# infant.net
KiCad netlist of a schematic drawn in EAGLE
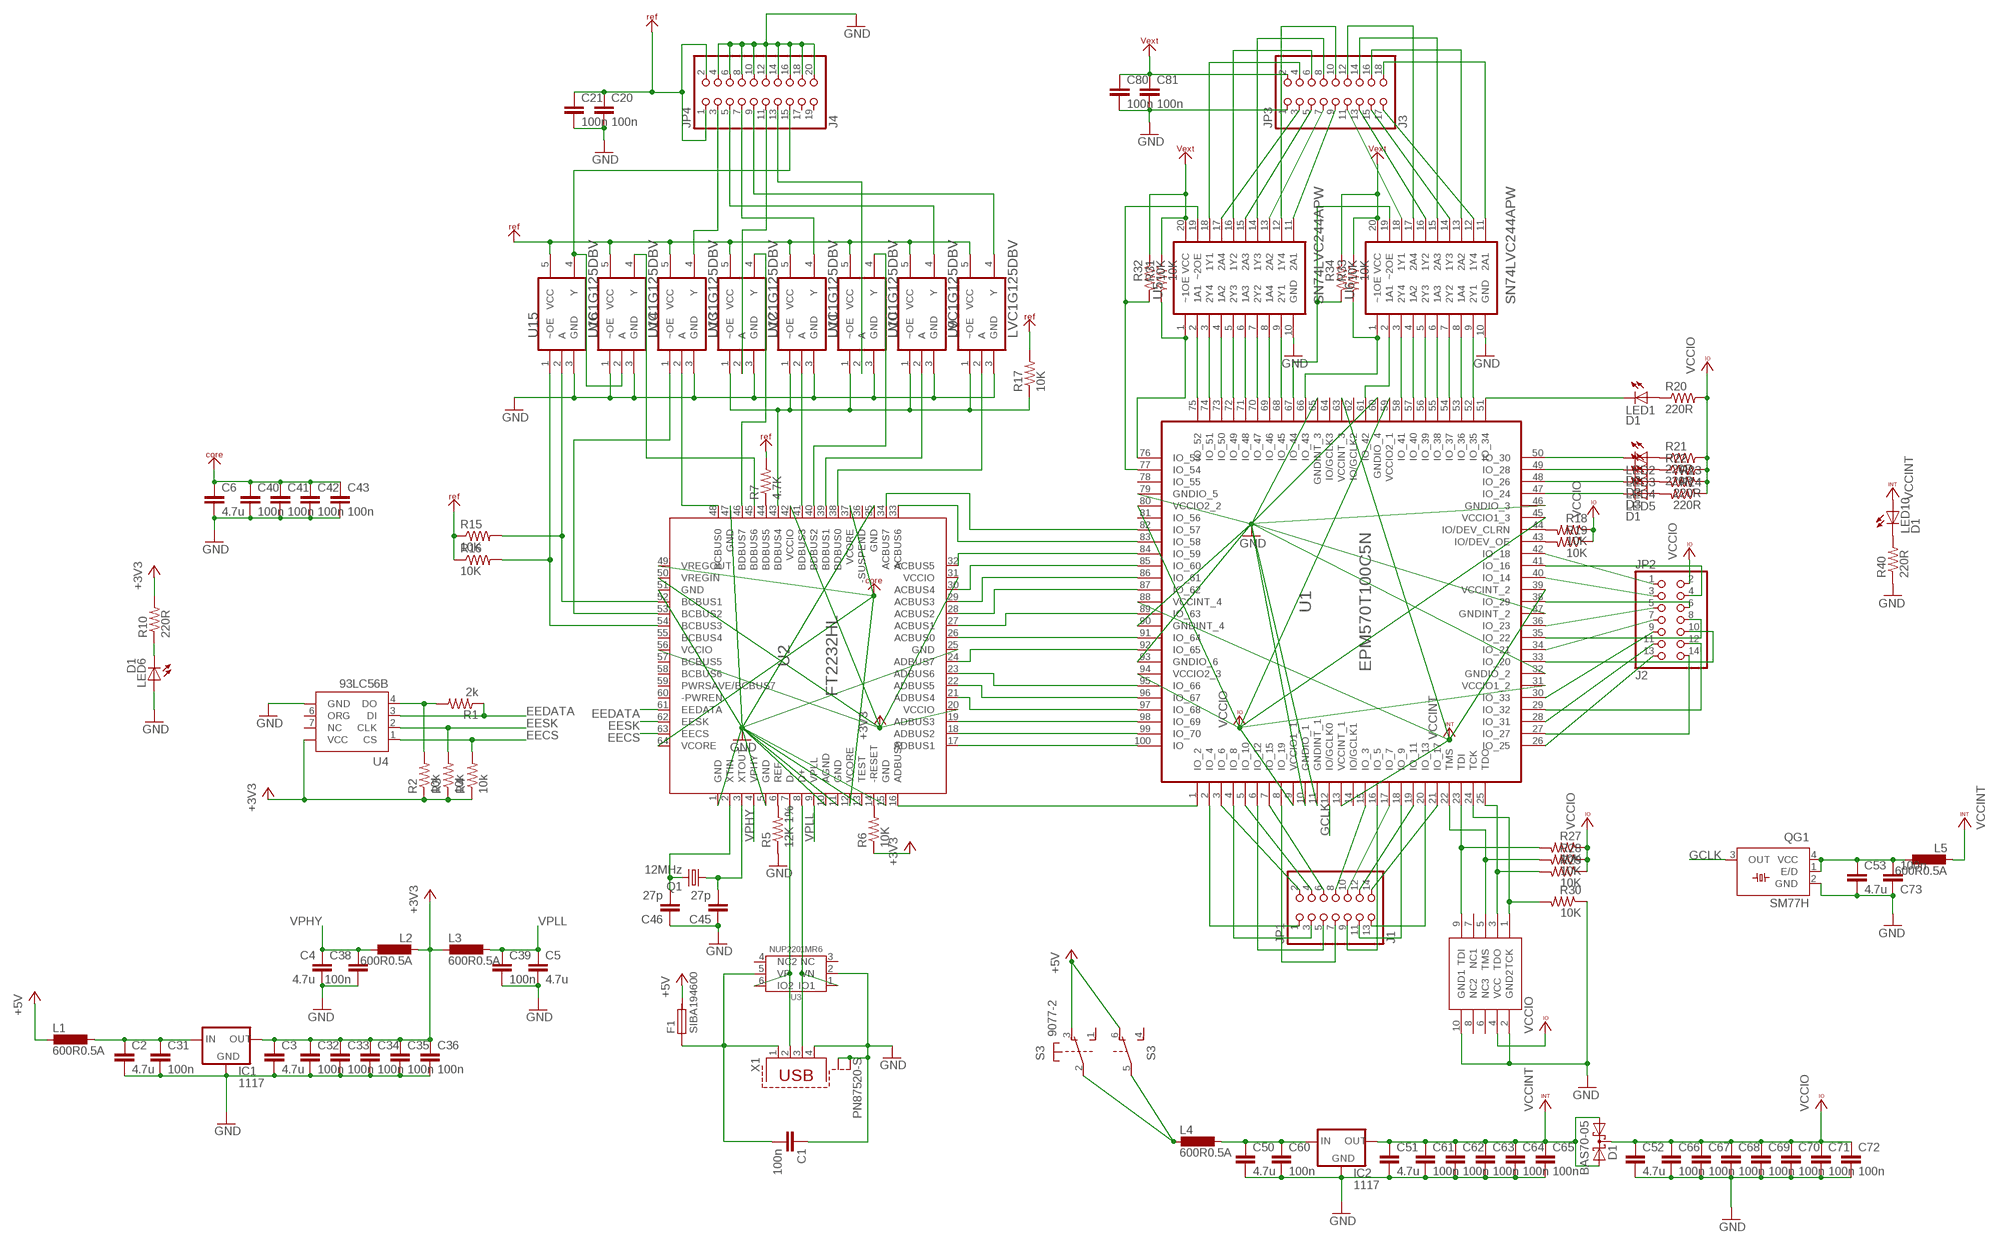
[diagram p0: schematic, sheet 1]

(export (version "E")
  (design (tool "Eeschema 10.0.6"))
  (components
    (comp (ref "C1")
      (value "100n")
      (footprint "eagle-import:C0805")
      (libsource (lib "eagle-import") (part "C-EUC0805"))
    )
    (comp (ref "C2")
      (value "4.7u")
      (footprint "eagle-import:C0805K")
      (libsource (lib "eagle-import") (part "C-EUC0805K"))
    )
    (comp (ref "C3")
      (value "4.7u")
      (footprint "eagle-import:C0805K")
      (libsource (lib "eagle-import") (part "C-EUC0805K"))
    )
    (comp (ref "C4")
      (value "4.7u")
      (footprint "eagle-import:C0805K")
      (libsource (lib "eagle-import") (part "C-EUC0805K"))
    )
    (comp (ref "C5")
      (value "4.7u")
      (footprint "eagle-import:C0805K")
      (libsource (lib "eagle-import") (part "C-EUC0805K"))
    )
    (comp (ref "C6")
      (value "4.7u")
      (footprint "eagle-import:C0805K")
      (libsource (lib "eagle-import") (part "C-EUC0805K"))
    )
    (comp (ref "C20")
      (value "100n")
      (footprint "eagle-import:C0805")
      (libsource (lib "eagle-import") (part "C-EUC0805"))
    )
    (comp (ref "C21")
      (value "100n")
      (footprint "eagle-import:C0805")
      (libsource (lib "eagle-import") (part "C-EUC0805"))
    )
    (comp (ref "C31")
      (value "100n")
      (footprint "eagle-import:C0805")
      (libsource (lib "eagle-import") (part "C-EUC0805"))
    )
    (comp (ref "C32")
      (value "100n")
      (footprint "eagle-import:C0805")
      (libsource (lib "eagle-import") (part "C-EUC0805"))
    )
    (comp (ref "C33")
      (value "100n")
      (footprint "eagle-import:C0805")
      (libsource (lib "eagle-import") (part "C-EUC0805"))
    )
    (comp (ref "C34")
      (value "100n")
      (footprint "eagle-import:C0805")
      (libsource (lib "eagle-import") (part "C-EUC0805"))
    )
    (comp (ref "C35")
      (value "100n")
      (footprint "eagle-import:C0805")
      (libsource (lib "eagle-import") (part "C-EUC0805"))
    )
    (comp (ref "C36")
      (value "100n")
      (footprint "eagle-import:C0805")
      (libsource (lib "eagle-import") (part "C-EUC0805"))
    )
    (comp (ref "C38")
      (value "100n")
      (footprint "eagle-import:C0805")
      (libsource (lib "eagle-import") (part "C-EUC0805"))
    )
    (comp (ref "C39")
      (value "100n")
      (footprint "eagle-import:C0805")
      (libsource (lib "eagle-import") (part "C-EUC0805"))
    )
    (comp (ref "C40")
      (value "100n")
      (footprint "eagle-import:C0805")
      (libsource (lib "eagle-import") (part "C-EUC0805"))
    )
    (comp (ref "C41")
      (value "100n")
      (footprint "eagle-import:C0805")
      (libsource (lib "eagle-import") (part "C-EUC0805"))
    )
    (comp (ref "C42")
      (value "100n")
      (footprint "eagle-import:C0805")
      (libsource (lib "eagle-import") (part "C-EUC0805"))
    )
    (comp (ref "C43")
      (value "100n")
      (footprint "eagle-import:C0805")
      (libsource (lib "eagle-import") (part "C-EUC0805"))
    )
    (comp (ref "C45")
      (value "27p")
      (footprint "eagle-import:C025-025X050")
      (libsource (lib "eagle-import") (part "C-EU025-025X050"))
    )
    (comp (ref "C46")
      (value "27p")
      (footprint "eagle-import:C025-025X050")
      (libsource (lib "eagle-import") (part "C-EU025-025X050"))
    )
    (comp (ref "C50")
      (value "4.7u")
      (footprint "eagle-import:C0805K")
      (libsource (lib "eagle-import") (part "C-EUC0805K"))
    )
    (comp (ref "C51")
      (value "4.7u")
      (footprint "eagle-import:C0805K")
      (libsource (lib "eagle-import") (part "C-EUC0805K"))
    )
    (comp (ref "C52")
      (value "4.7u")
      (footprint "eagle-import:C0805K")
      (libsource (lib "eagle-import") (part "C-EUC0805K"))
    )
    (comp (ref "C53")
      (value "4.7u")
      (footprint "eagle-import:C0805K")
      (libsource (lib "eagle-import") (part "C-EUC0805K"))
    )
    (comp (ref "C60")
      (value "100n")
      (footprint "eagle-import:C0805")
      (libsource (lib "eagle-import") (part "C-EUC0805"))
    )
    (comp (ref "C61")
      (value "100n")
      (footprint "eagle-import:C0805")
      (libsource (lib "eagle-import") (part "C-EUC0805"))
    )
    (comp (ref "C62")
      (value "100n")
      (footprint "eagle-import:C0805")
      (libsource (lib "eagle-import") (part "C-EUC0805"))
    )
    (comp (ref "C63")
      (value "100n")
      (footprint "eagle-import:C0805")
      (libsource (lib "eagle-import") (part "C-EUC0805"))
    )
    (comp (ref "C64")
      (value "100n")
      (footprint "eagle-import:C0805")
      (libsource (lib "eagle-import") (part "C-EUC0805"))
    )
    (comp (ref "C65")
      (value "100n")
      (footprint "eagle-import:C0805")
      (libsource (lib "eagle-import") (part "C-EUC0805"))
    )
    (comp (ref "C66")
      (value "100n")
      (footprint "eagle-import:C0805")
      (libsource (lib "eagle-import") (part "C-EUC0805"))
    )
    (comp (ref "C67")
      (value "100n")
      (footprint "eagle-import:C0805")
      (libsource (lib "eagle-import") (part "C-EUC0805"))
    )
    (comp (ref "C68")
      (value "100n")
      (footprint "eagle-import:C0805")
      (libsource (lib "eagle-import") (part "C-EUC0805"))
    )
    (comp (ref "C69")
      (value "100n")
      (footprint "eagle-import:C0805")
      (libsource (lib "eagle-import") (part "C-EUC0805"))
    )
    (comp (ref "C70")
      (value "100n")
      (footprint "eagle-import:C0805")
      (libsource (lib "eagle-import") (part "C-EUC0805"))
    )
    (comp (ref "C71")
      (value "100n")
      (footprint "eagle-import:C0805")
      (libsource (lib "eagle-import") (part "C-EUC0805"))
    )
    (comp (ref "C72")
      (value "100n")
      (footprint "eagle-import:C0805")
      (libsource (lib "eagle-import") (part "C-EUC0805"))
    )
    (comp (ref "C73")
      (value "100n")
      (footprint "eagle-import:C0805")
      (libsource (lib "eagle-import") (part "C-EUC0805"))
    )
    (comp (ref "C80")
      (value "100n")
      (footprint "eagle-import:C0805")
      (libsource (lib "eagle-import") (part "C-EUC0805"))
    )
    (comp (ref "C81")
      (value "100n")
      (footprint "eagle-import:C0805")
      (libsource (lib "eagle-import") (part "C-EUC0805"))
    )
    (comp (ref "D1")
      (value "BAS70-05")
      (footprint "eagle-import:SOT23")
      (libsource (lib "eagle-import") (part "BAS70-05"))
    )
    (comp (ref "F1")
      (value "SIBA194600")
      (footprint "eagle-import:C1812")
      (libsource (lib "eagle-import") (part "SIBA194600"))
    )
    (comp (ref "IC1")
      (value "1117")
      (footprint "eagle-import:SOT223")
      (libsource (lib "eagle-import") (part "LM1117"))
    )
    (comp (ref "IC2")
      (value "1117")
      (footprint "eagle-import:SOT223")
      (libsource (lib "eagle-import") (part "LM1117"))
    )
    (comp (ref "JP1")
      (value "J1")
      (footprint "eagle-import:2X07")
      (libsource (lib "eagle-import") (part "PINHD-2X7"))
    )
    (comp (ref "JP2")
      (value "J2")
      (footprint "eagle-import:2X07")
      (libsource (lib "eagle-import") (part "PINHD-2X7"))
    )
    (comp (ref "JP3")
      (value "J3")
      (footprint "eagle-import:2X09")
      (libsource (lib "eagle-import") (part "PINHD-2X9"))
    )
    (comp (ref "JP4")
      (value "J4")
      (footprint "eagle-import:2X10")
      (libsource (lib "eagle-import") (part "PINHD-2X10"))
    )
    (comp (ref "L1")
      (value "600R0.5A")
      (footprint "eagle-import:R0805")
      (libsource (lib "eagle-import") (part "DO3316P"))
    )
    (comp (ref "L2")
      (value "600R0.5A")
      (footprint "eagle-import:R0805")
      (libsource (lib "eagle-import") (part "DO3316P"))
    )
    (comp (ref "L3")
      (value "600R0.5A")
      (footprint "eagle-import:R0805")
      (libsource (lib "eagle-import") (part "DO3316P"))
    )
    (comp (ref "L4")
      (value "600R0.5A")
      (footprint "eagle-import:R0805")
      (libsource (lib "eagle-import") (part "DO3316P"))
    )
    (comp (ref "L5")
      (value "600R0.5A")
      (footprint "eagle-import:R0805")
      (libsource (lib "eagle-import") (part "DO3316P"))
    )
    (comp (ref "LED1")
      (value "D1")
      (footprint "eagle-import:CHIPLED_0805")
      (libsource (lib "eagle-import") (part "LEDCHIPLED_0805"))
    )
    (comp (ref "LED2")
      (value "D2")
      (footprint "eagle-import:CHIPLED_0805")
      (libsource (lib "eagle-import") (part "LEDCHIPLED_0805"))
    )
    (comp (ref "LED3")
      (value "D3")
      (footprint "eagle-import:CHIPLED_0805")
      (libsource (lib "eagle-import") (part "LEDCHIPLED_0805"))
    )
    (comp (ref "LED4")
      (value "D3")
      (footprint "eagle-import:CHIPLED_0805")
      (libsource (lib "eagle-import") (part "LEDCHIPLED_0805"))
    )
    (comp (ref "LED5")
      (value "D1")
      (footprint "eagle-import:CHIPLED_0805")
      (libsource (lib "eagle-import") (part "LEDCHIPLED_0805"))
    )
    (comp (ref "LED6")
      (value "D1")
      (footprint "eagle-import:CHIPLED_0805")
      (libsource (lib "eagle-import") (part "LEDCHIPLED_0805"))
    )
    (comp (ref "LED10")
      (value "D1")
      (footprint "eagle-import:CHIPLED_0805")
      (libsource (lib "eagle-import") (part "LEDCHIPLED_0805"))
    )
    (comp (ref "Q1")
      (value "12MHz")
      (footprint "eagle-import:HC49_S")
      (libsource (lib "eagle-import") (part "CRYSTALHC49S"))
    )
    (comp (ref "QG1")
      (value "SM77H")
      (footprint "eagle-import:SM77H")
      (libsource (lib "eagle-import") (part "SM77H"))
    )
    (comp (ref "R1")
      (value "2k")
      (footprint "eagle-import:R0805")
      (libsource (lib "eagle-import") (part "R-US_R0805"))
    )
    (comp (ref "R2")
      (value "10k")
      (footprint "eagle-import:R0805")
      (libsource (lib "eagle-import") (part "R-US_R0805"))
    )
    (comp (ref "R3")
      (value "10k")
      (footprint "eagle-import:R0805")
      (libsource (lib "eagle-import") (part "R-US_R0805"))
    )
    (comp (ref "R4")
      (value "10k")
      (footprint "eagle-import:R0805")
      (libsource (lib "eagle-import") (part "R-US_R0805"))
    )
    (comp (ref "R5")
      (value "12K 1%")
      (footprint "eagle-import:R0805")
      (libsource (lib "eagle-import") (part "R-US_R0805"))
    )
    (comp (ref "R6")
      (value "10K")
      (footprint "eagle-import:R0805")
      (libsource (lib "eagle-import") (part "R-US_R0805"))
    )
    (comp (ref "R7")
      (value "4.7K")
      (footprint "eagle-import:R0805")
      (libsource (lib "eagle-import") (part "R-US_R0805"))
    )
    (comp (ref "R10")
      (value "220R")
      (footprint "eagle-import:R0805")
      (libsource (lib "eagle-import") (part "R-US_R0805"))
    )
    (comp (ref "R15")
      (value "10K")
      (footprint "eagle-import:R0805")
      (libsource (lib "eagle-import") (part "R-US_R0805"))
    )
    (comp (ref "R16")
      (value "10K")
      (footprint "eagle-import:R0805")
      (libsource (lib "eagle-import") (part "R-US_R0805"))
    )
    (comp (ref "R17")
      (value "10K")
      (footprint "eagle-import:R0805")
      (libsource (lib "eagle-import") (part "R-US_R0805"))
    )
    (comp (ref "R18")
      (value "10K")
      (footprint "eagle-import:R0805")
      (libsource (lib "eagle-import") (part "R-US_R0805"))
    )
    (comp (ref "R19")
      (value "10K")
      (footprint "eagle-import:R0805")
      (libsource (lib "eagle-import") (part "R-US_R0805"))
    )
    (comp (ref "R20")
      (value "220R")
      (footprint "eagle-import:R0805")
      (libsource (lib "eagle-import") (part "R-US_R0805"))
    )
    (comp (ref "R21")
      (value "220R")
      (footprint "eagle-import:R0805")
      (libsource (lib "eagle-import") (part "R-US_R0805"))
    )
    (comp (ref "R22")
      (value "220R")
      (footprint "eagle-import:R0805")
      (libsource (lib "eagle-import") (part "R-US_R0805"))
    )
    (comp (ref "R23")
      (value "220R")
      (footprint "eagle-import:R0805")
      (libsource (lib "eagle-import") (part "R-US_R0805"))
    )
    (comp (ref "R24")
      (value "220R")
      (footprint "eagle-import:R0805")
      (libsource (lib "eagle-import") (part "R-US_R0805"))
    )
    (comp (ref "R27")
      (value "10K")
      (footprint "eagle-import:R0805")
      (libsource (lib "eagle-import") (part "R-US_R0805"))
    )
    (comp (ref "R28")
      (value "10K")
      (footprint "eagle-import:R0805")
      (libsource (lib "eagle-import") (part "R-US_R0805"))
    )
    (comp (ref "R29")
      (value "10K")
      (footprint "eagle-import:R0805")
      (libsource (lib "eagle-import") (part "R-US_R0805"))
    )
    (comp (ref "R30")
      (value "10K")
      (footprint "eagle-import:R0805")
      (libsource (lib "eagle-import") (part "R-US_R0805"))
    )
    (comp (ref "R31")
      (value "10K")
      (footprint "eagle-import:R0805")
      (libsource (lib "eagle-import") (part "R-US_R0805"))
    )
    (comp (ref "R32")
      (value "10K")
      (footprint "eagle-import:R0805")
      (libsource (lib "eagle-import") (part "R-US_R0805"))
    )
    (comp (ref "R33")
      (value "10K")
      (footprint "eagle-import:R0805")
      (libsource (lib "eagle-import") (part "R-US_R0805"))
    )
    (comp (ref "R34")
      (value "10K")
      (footprint "eagle-import:R0805")
      (libsource (lib "eagle-import") (part "R-US_R0805"))
    )
    (comp (ref "R40")
      (value "220R")
      (footprint "eagle-import:R0805")
      (libsource (lib "eagle-import") (part "R-US_R0805"))
    )
    (comp (ref "S3")
      (value "9077-2")
      (footprint "eagle-import:9077-2")
      (libsource (lib "eagle-import") (part "9077-2"))
    )
    (comp (ref "U$2")
      (value "BOXHEADER10JTAG")
      (footprint "eagle-import:ML10")
      (libsource (lib "eagle-import") (part "BOXHEADER10JTAG"))
    )
    (comp (ref "U1")
      (value "EPM570T100C5N")
      (footprint "eagle-import:TQFP100")
      (libsource (lib "eagle-import") (part "SQUARE-QFP"))
    )
    (comp (ref "U2")
      (value "FT2232HL")
      (footprint "eagle-import:LQFP-64")
      (libsource (lib "eagle-import") (part "FT2232HL"))
    )
    (comp (ref "U3")
      (value "NUP2201MR6")
      (footprint "eagle-import:TSOP6")
      (libsource (lib "eagle-import") (part "NUP2201MR6"))
    )
    (comp (ref "U4")
      (value "93LC56B")
      (footprint "eagle-import:SOIC8")
      (libsource (lib "eagle-import") (part "PIN2PIN-SOIC8"))
    )
    (comp (ref "U5")
      (value "SN74LVC244APW")
      (footprint "eagle-import:TSSOP20")
      (libsource (lib "eagle-import") (part "SN74LVC244APW"))
    )
    (comp (ref "U6")
      (value "SN74LVC244APW")
      (footprint "eagle-import:TSSOP20")
      (libsource (lib "eagle-import") (part "SN74LVC244APW"))
    )
    (comp (ref "U9")
      (value "LVC1G125DBV")
      (footprint "eagle-import:SOT23-5")
      (fields (field (name "MPN") "SN74LVC1G125DBVR"))
      (libsource (lib "eagle-import") (part "SN74LVC1G125DBVR"))
    )
    (comp (ref "U10")
      (value "LVC1G125DBV")
      (footprint "eagle-import:SOT23-5")
      (fields (field (name "MPN") "SN74LVC1G125DBVR"))
      (libsource (lib "eagle-import") (part "SN74LVC1G125DBVR"))
    )
    (comp (ref "U11")
      (value "LVC1G125DBV")
      (footprint "eagle-import:SOT23-5")
      (fields (field (name "MPN") "SN74LVC1G125DBVR"))
      (libsource (lib "eagle-import") (part "SN74LVC1G125DBVR"))
    )
    (comp (ref "U12")
      (value "LVC1G125DBV")
      (footprint "eagle-import:SOT23-5")
      (fields (field (name "MPN") "SN74LVC1G125DBVR"))
      (libsource (lib "eagle-import") (part "SN74LVC1G125DBVR"))
    )
    (comp (ref "U13")
      (value "LVC1G125DBV")
      (footprint "eagle-import:SOT23-5")
      (fields (field (name "MPN") "SN74LVC1G125DBVR"))
      (libsource (lib "eagle-import") (part "SN74LVC1G125DBVR"))
    )
    (comp (ref "U14")
      (value "LVC1G125DBV")
      (footprint "eagle-import:SOT23-5")
      (fields (field (name "MPN") "SN74LVC1G125DBVR"))
      (libsource (lib "eagle-import") (part "SN74LVC1G125DBVR"))
    )
    (comp (ref "U15")
      (value "LVC1G125DBV")
      (footprint "eagle-import:SOT23-5")
      (fields (field (name "MPN") "SN74LVC1G125DBVR"))
      (libsource (lib "eagle-import") (part "SN74LVC1G125DBVR"))
    )
    (comp (ref "U16")
      (value "LVC1G125DBV")
      (footprint "eagle-import:SOT23-5")
      (fields (field (name "MPN") "SN74LVC1G125DBVR"))
      (libsource (lib "eagle-import") (part "SN74LVC1G125DBVR"))
    )
    (comp (ref "X1")
      (value "PN87520-S")
      (footprint "eagle-import:USB")
      (libsource (lib "eagle-import") (part "PN87520-S"))
    )
  )
  (nets
    (net (code "1") (name "+3V3") (class "Default")
      (node (ref "C3") (pin "1") (pinfunction "1_1") (pintype "passive"))
      (node (ref "C32") (pin "1") (pinfunction "1_1") (pintype "passive"))
      (node (ref "C33") (pin "1") (pinfunction "1_1") (pintype "passive"))
      (node (ref "C34") (pin "1") (pinfunction "1_1") (pintype "passive"))
      (node (ref "C35") (pin "1") (pinfunction "1_1") (pintype "passive"))
      (node (ref "C36") (pin "1") (pinfunction "1_1") (pintype "passive"))
      (node (ref "IC1") (pin "2") (pinfunction "OUT_2") (pintype "passive"))
      (node (ref "L2") (pin "1") (pinfunction "1_1") (pintype "passive"))
      (node (ref "L3") (pin "1") (pinfunction "1_1") (pintype "passive"))
      (node (ref "R10") (pin "2") (pinfunction "2_2") (pintype "passive"))
      (node (ref "R2") (pin "1") (pinfunction "1_1") (pintype "passive"))
      (node (ref "R3") (pin "1") (pinfunction "1_1") (pintype "passive"))
      (node (ref "R4") (pin "1") (pinfunction "1_1") (pintype "passive"))
      (node (ref "R6") (pin "1") (pinfunction "1_1") (pintype "passive"))
      (node (ref "U2") (pin "20") (pinfunction "VCCIO_20") (pintype "power_in"))
      (node (ref "U2") (pin "31") (pinfunction "VCCIO_31") (pintype "power_in"))
      (node (ref "U2") (pin "42") (pinfunction "VCCIO_42") (pintype "power_in"))
      (node (ref "U2") (pin "50") (pinfunction "VREGIN_50") (pintype "input"))
      (node (ref "U2") (pin "56") (pinfunction "VCCIO_56") (pintype "power_in"))
      (node (ref "U4") (pin "8") (pinfunction "VCC_8") (pintype "power_in"))
    )
    (net (code "2") (name "+5V") (class "Default")
      (node (ref "F1") (pin "2") (pinfunction "2_2") (pintype "passive"))
      (node (ref "L1") (pin "1") (pinfunction "1_1") (pintype "passive"))
      (node (ref "S3") (pin "3") (pinfunction "O_3") (pintype "passive"))
      (node (ref "S3") (pin "6") (pinfunction "O_6") (pintype "passive"))
    )
    (net (code "3") (name "/EECS") (class "Default")
      (node (ref "R4") (pin "2") (pinfunction "2_2") (pintype "passive"))
      (node (ref "U2") (pin "63") (pinfunction "EECS_63") (pintype "output"))
      (node (ref "U4") (pin "1") (pinfunction "CS_1") (pintype "input"))
    )
    (net (code "4") (name "/EEDATA") (class "Default")
      (node (ref "R1") (pin "1") (pinfunction "1_1") (pintype "passive"))
      (node (ref "U2") (pin "61") (pinfunction "EEDATA_61") (pintype "input"))
      (node (ref "U4") (pin "3") (pinfunction "DI_3") (pintype "input"))
    )
    (net (code "5") (name "/EESK") (class "Default")
      (node (ref "R3") (pin "2") (pinfunction "2_2") (pintype "passive"))
      (node (ref "U2") (pin "62") (pinfunction "EESK_62") (pintype "output"))
      (node (ref "U4") (pin "2") (pinfunction "CLK_2") (pintype "input"))
    )
    (net (code "6") (name "/GCLK") (class "Default")
      (node (ref "QG1") (pin "3") (pinfunction "OUT_3") (pintype "output"))
      (node (ref "U1") (pin "12") (pinfunction "IO/GCLK0_12") (pintype "bidirectional"))
    )
    (net (code "7") (name "/VPHY") (class "Default")
      (node (ref "C38") (pin "1") (pinfunction "1_1") (pintype "passive"))
      (node (ref "C4") (pin "1") (pinfunction "1_1") (pintype "passive"))
      (node (ref "L2") (pin "2") (pinfunction "2_2") (pintype "passive"))
      (node (ref "U2") (pin "4") (pinfunction "VPHY_4") (pintype "power_in"))
    )
    (net (code "8") (name "/VPLL") (class "Default")
      (node (ref "C39") (pin "1") (pinfunction "1_1") (pintype "passive"))
      (node (ref "C5") (pin "1") (pinfunction "1_1") (pintype "passive"))
      (node (ref "L3") (pin "2") (pinfunction "2_2") (pintype "passive"))
      (node (ref "U2") (pin "9") (pinfunction "VPLL_9") (pintype "power_in"))
    )
    (net (code "9") (name "GND") (class "Default")
      (node (ref "C1") (pin "1") (pinfunction "1_1") (pintype "passive"))
      (node (ref "C2") (pin "2") (pinfunction "2_2") (pintype "passive"))
      (node (ref "C20") (pin "2") (pinfunction "2_2") (pintype "passive"))
      (node (ref "C21") (pin "2") (pinfunction "2_2") (pintype "passive"))
      (node (ref "C3") (pin "2") (pinfunction "2_2") (pintype "passive"))
      (node (ref "C31") (pin "2") (pinfunction "2_2") (pintype "passive"))
      (node (ref "C32") (pin "2") (pinfunction "2_2") (pintype "passive"))
      (node (ref "C33") (pin "2") (pinfunction "2_2") (pintype "passive"))
      (node (ref "C34") (pin "2") (pinfunction "2_2") (pintype "passive"))
      (node (ref "C35") (pin "2") (pinfunction "2_2") (pintype "passive"))
      (node (ref "C36") (pin "2") (pinfunction "2_2") (pintype "passive"))
      (node (ref "C38") (pin "2") (pinfunction "2_2") (pintype "passive"))
      (node (ref "C39") (pin "2") (pinfunction "2_2") (pintype "passive"))
      (node (ref "C4") (pin "2") (pinfunction "2_2") (pintype "passive"))
      (node (ref "C40") (pin "2") (pinfunction "2_2") (pintype "passive"))
      (node (ref "C41") (pin "2") (pinfunction "2_2") (pintype "passive"))
      (node (ref "C42") (pin "2") (pinfunction "2_2") (pintype "passive"))
      (node (ref "C43") (pin "2") (pinfunction "2_2") (pintype "passive"))
      (node (ref "C45") (pin "1") (pinfunction "1_1") (pintype "passive"))
      (node (ref "C46") (pin "1") (pinfunction "1_1") (pintype "passive"))
      (node (ref "C5") (pin "2") (pinfunction "2_2") (pintype "passive"))
      (node (ref "C50") (pin "2") (pinfunction "2_2") (pintype "passive"))
      (node (ref "C51") (pin "2") (pinfunction "2_2") (pintype "passive"))
      (node (ref "C52") (pin "2") (pinfunction "2_2") (pintype "passive"))
      (node (ref "C53") (pin "2") (pinfunction "2_2") (pintype "passive"))
      (node (ref "C6") (pin "2") (pinfunction "2_2") (pintype "passive"))
      (node (ref "C60") (pin "2") (pinfunction "2_2") (pintype "passive"))
      (node (ref "C61") (pin "2") (pinfunction "2_2") (pintype "passive"))
      (node (ref "C62") (pin "2") (pinfunction "2_2") (pintype "passive"))
      (node (ref "C63") (pin "2") (pinfunction "2_2") (pintype "passive"))
      (node (ref "C64") (pin "2") (pinfunction "2_2") (pintype "passive"))
      (node (ref "C65") (pin "2") (pinfunction "2_2") (pintype "passive"))
      (node (ref "C66") (pin "2") (pinfunction "2_2") (pintype "passive"))
      (node (ref "C67") (pin "2") (pinfunction "2_2") (pintype "passive"))
      (node (ref "C68") (pin "2") (pinfunction "2_2") (pintype "passive"))
      (node (ref "C69") (pin "2") (pinfunction "2_2") (pintype "passive"))
      (node (ref "C70") (pin "2") (pinfunction "2_2") (pintype "passive"))
      (node (ref "C71") (pin "2") (pinfunction "2_2") (pintype "passive"))
      (node (ref "C72") (pin "2") (pinfunction "2_2") (pintype "passive"))
      (node (ref "C73") (pin "1") (pinfunction "1_1") (pintype "passive"))
      (node (ref "C80") (pin "2") (pinfunction "2_2") (pintype "passive"))
      (node (ref "C81") (pin "2") (pinfunction "2_2") (pintype "passive"))
      (node (ref "IC1") (pin "1") (pinfunction "GND_1") (pintype "input"))
      (node (ref "IC2") (pin "1") (pinfunction "GND_1") (pintype "input"))
      (node (ref "JP3") (pin "1") (pinfunction "1_1") (pintype "passive"))
      (node (ref "JP4") (pin "10") (pinfunction "10_10") (pintype "passive"))
      (node (ref "JP4") (pin "12") (pinfunction "12_12") (pintype "passive"))
      (node (ref "JP4") (pin "14") (pinfunction "14_14") (pintype "passive"))
      (node (ref "JP4") (pin "16") (pinfunction "16_16") (pintype "passive"))
      (node (ref "JP4") (pin "18") (pinfunction "18_18") (pintype "passive"))
      (node (ref "JP4") (pin "20") (pinfunction "20_20") (pintype "passive"))
      (node (ref "JP4") (pin "4") (pinfunction "4_4") (pintype "passive"))
      (node (ref "JP4") (pin "6") (pinfunction "6_6") (pintype "passive"))
      (node (ref "JP4") (pin "8") (pinfunction "8_8") (pintype "passive"))
      (node (ref "LED6") (pin "A") (pinfunction "A_A") (pintype "passive"))
      (node (ref "QG1") (pin "2") (pinfunction "GND_2") (pintype "power_in"))
      (node (ref "R30") (pin "1") (pinfunction "1_1") (pintype "passive"))
      (node (ref "R40") (pin "1") (pinfunction "1_1") (pintype "passive"))
      (node (ref "R5") (pin "1") (pinfunction "1_1") (pintype "passive"))
      (node (ref "U$2") (pin "10") (pinfunction "GND1_10") (pintype "bidirectional"))
      (node (ref "U$2") (pin "2") (pinfunction "GND2_2") (pintype "bidirectional"))
      (node (ref "U1") (pin "10") (pinfunction "GNDIO_1_10") (pintype "passive"))
      (node (ref "U1") (pin "11") (pinfunction "GNDINT_1_11") (pintype "passive"))
      (node (ref "U1") (pin "32") (pinfunction "GNDIO_2_32") (pintype "passive"))
      (node (ref "U1") (pin "37") (pinfunction "GNDINT_2_37") (pintype "passive"))
      (node (ref "U1") (pin "46") (pinfunction "GNDIO_3_46") (pintype "passive"))
      (node (ref "U1") (pin "60") (pinfunction "GNDIO_4_60") (pintype "passive"))
      (node (ref "U1") (pin "65") (pinfunction "GNDINT_3_65") (pintype "passive"))
      (node (ref "U1") (pin "79") (pinfunction "GNDIO_5_79") (pintype "passive"))
      (node (ref "U1") (pin "90") (pinfunction "GNDINT_4_90") (pintype "passive"))
      (node (ref "U1") (pin "93") (pinfunction "GNDIO_6_93") (pintype "passive"))
      (node (ref "U10") (pin "3") (pinfunction "GND_3") (pintype "passive"))
      (node (ref "U11") (pin "3") (pinfunction "GND_3") (pintype "passive"))
      (node (ref "U12") (pin "3") (pinfunction "GND_3") (pintype "passive"))
      (node (ref "U13") (pin "3") (pinfunction "GND_3") (pintype "passive"))
      (node (ref "U14") (pin "3") (pinfunction "GND_3") (pintype "passive"))
      (node (ref "U15") (pin "3") (pinfunction "GND_3") (pintype "passive"))
      (node (ref "U16") (pin "1") (pinfunction "~{OE}_1") (pintype "input"))
      (node (ref "U16") (pin "3") (pinfunction "GND_3") (pintype "passive"))
      (node (ref "U2") (pin "1") (pinfunction "GND_1") (pintype "power_in"))
      (node (ref "U2") (pin "10") (pinfunction "AGND_10") (pintype "power_in"))
      (node (ref "U2") (pin "11") (pinfunction "GND_11") (pintype "power_in"))
      (node (ref "U2") (pin "13") (pinfunction "TEST_13") (pintype "input"))
      (node (ref "U2") (pin "15") (pinfunction "GND_15") (pintype "power_in"))
      (node (ref "U2") (pin "25") (pinfunction "GND_25") (pintype "power_in"))
      (node (ref "U2") (pin "35") (pinfunction "GND_35") (pintype "power_in"))
      (node (ref "U2") (pin "47") (pinfunction "GND_47") (pintype "power_in"))
      (node (ref "U2") (pin "5") (pinfunction "GND_5") (pintype "power_in"))
      (node (ref "U2") (pin "51") (pinfunction "GND_51") (pintype "power_in"))
      (node (ref "U3") (pin "2") (pinfunction "VN_2") (pintype "bidirectional"))
      (node (ref "U4") (pin "5") (pinfunction "GND_5") (pintype "power_in"))
      (node (ref "U5") (pin "10") (pinfunction "GND_10") (pintype "passive"))
      (node (ref "U6") (pin "10") (pinfunction "GND_10") (pintype "passive"))
      (node (ref "U9") (pin "3") (pinfunction "GND_3") (pintype "passive"))
      (node (ref "X1") (pin "4") (pinfunction "4_4") (pintype "passive"))
      (node (ref "X1") (pin "S1") (pinfunction "S1_S1") (pintype "passive"))
      (node (ref "X1") (pin "S2") (pinfunction "S2_S2") (pintype "passive"))
    )
    (net (code "10") (name "Net-(IC1-IN)") (class "Default")
      (node (ref "C2") (pin "1") (pinfunction "1_1") (pintype "passive"))
      (node (ref "C31") (pin "1") (pinfunction "1_1") (pintype "passive"))
      (node (ref "IC1") (pin "3") (pinfunction "IN_3") (pintype "input"))
      (node (ref "L1") (pin "2") (pinfunction "2_2") (pintype "passive"))
    )
    (net (code "11") (name "Net-(IC2-IN)") (class "Default")
      (node (ref "C50") (pin "1") (pinfunction "1_1") (pintype "passive"))
      (node (ref "C60") (pin "1") (pinfunction "1_1") (pintype "passive"))
      (node (ref "IC2") (pin "3") (pinfunction "IN_3") (pintype "input"))
      (node (ref "L4") (pin "2") (pinfunction "2_2") (pintype "passive"))
    )
    (net (code "12") (name "Net-(LED1-PadA)") (class "Default")
      (node (ref "LED1") (pin "A") (pinfunction "A_A") (pintype "passive"))
      (node (ref "R20") (pin "1") (pinfunction "1_1") (pintype "passive"))
    )
    (net (code "13") (name "Net-(LED2-PadA)") (class "Default")
      (node (ref "LED2") (pin "A") (pinfunction "A_A") (pintype "passive"))
      (node (ref "R21") (pin "1") (pinfunction "1_1") (pintype "passive"))
    )
    (net (code "14") (name "Net-(LED3-PadA)") (class "Default")
      (node (ref "LED3") (pin "A") (pinfunction "A_A") (pintype "passive"))
      (node (ref "R22") (pin "1") (pinfunction "1_1") (pintype "passive"))
    )
    (net (code "15") (name "Net-(LED4-PadA)") (class "Default")
      (node (ref "LED4") (pin "A") (pinfunction "A_A") (pintype "passive"))
      (node (ref "R23") (pin "2") (pinfunction "2_2") (pintype "passive"))
    )
    (net (code "16") (name "Net-(LED5-PadA)") (class "Default")
      (node (ref "LED5") (pin "A") (pinfunction "A_A") (pintype "passive"))
      (node (ref "R24") (pin "2") (pinfunction "2_2") (pintype "passive"))
    )
    (net (code "17") (name "Net-(LED6-PadC)") (class "Default")
      (node (ref "LED6") (pin "C") (pinfunction "C_C") (pintype "passive"))
      (node (ref "R10") (pin "1") (pinfunction "1_1") (pintype "passive"))
    )
    (net (code "18") (name "Net-(LED10-PadC)") (class "Default")
      (node (ref "LED10") (pin "C") (pinfunction "C_C") (pintype "passive"))
      (node (ref "R40") (pin "2") (pinfunction "2_2") (pintype "passive"))
    )
    (net (code "19") (name "Net-(QG1-E{slash}D)") (class "Default")
      (node (ref "C53") (pin "1") (pinfunction "1_1") (pintype "passive"))
      (node (ref "C73") (pin "2") (pinfunction "2_2") (pintype "passive"))
      (node (ref "L5") (pin "2") (pinfunction "2_2") (pintype "passive"))
      (node (ref "QG1") (pin "1") (pinfunction "E/D_1") (pintype "input"))
      (node (ref "QG1") (pin "4") (pinfunction "VCC_4") (pintype "power_in"))
    )
    (net (code "20") (name "Net-(S3A-P)") (class "Default")
      (node (ref "L4") (pin "1") (pinfunction "1_1") (pintype "passive"))
      (node (ref "S3") (pin "2") (pinfunction "P_2") (pintype "passive"))
      (node (ref "S3") (pin "5") (pinfunction "P_5") (pintype "passive"))
    )
    (net (code "21") (name "Net-(U$2-TCK)") (class "Default")
      (node (ref "R30") (pin "2") (pinfunction "2_2") (pintype "passive"))
      (node (ref "U$2") (pin "1") (pinfunction "TCK_1") (pintype "bidirectional"))
      (node (ref "U1") (pin "24") (pinfunction "TCK_24") (pintype "passive"))
    )
    (net (code "22") (name "Net-(U$2-TDI)") (class "Default")
      (node (ref "R27") (pin "2") (pinfunction "2_2") (pintype "passive"))
      (node (ref "U$2") (pin "9") (pinfunction "TDI_9") (pintype "bidirectional"))
      (node (ref "U1") (pin "23") (pinfunction "TDI_23") (pintype "passive"))
    )
    (net (code "23") (name "Net-(U$2-TDO)") (class "Default")
      (node (ref "R29") (pin "2") (pinfunction "2_2") (pintype "passive"))
      (node (ref "U$2") (pin "3") (pinfunction "TDO_3") (pintype "bidirectional"))
      (node (ref "U1") (pin "25") (pinfunction "TDO_25") (pintype "output"))
    )
    (net (code "24") (name "Net-(U$2-TMS)") (class "Default")
      (node (ref "R28") (pin "2") (pinfunction "2_2") (pintype "passive"))
      (node (ref "U$2") (pin "5") (pinfunction "TMS_5") (pintype "bidirectional"))
      (node (ref "U1") (pin "22") (pinfunction "TMS_22") (pintype "passive"))
    )
    (net (code "25") (name "Net-(U1-IO)") (class "Default")
      (node (ref "U1") (pin "100") (pinfunction "IO_100") (pintype "bidirectional"))
      (node (ref "U2") (pin "17") (pinfunction "ADBUS1_17") (pintype "bidirectional"))
    )
    (net (code "26") (name "Net-(U1-IO_2)") (class "Default")
      (node (ref "U1") (pin "1") (pinfunction "IO_2_1") (pintype "bidirectional"))
      (node (ref "U2") (pin "16") (pinfunction "ADBUS0_16") (pintype "bidirectional"))
    )
    (net (code "27") (name "Net-(U1-IO_3)") (class "Default")
      (node (ref "JP1") (pin "8") (pinfunction "8_8") (pintype "passive"))
      (node (ref "U1") (pin "15") (pinfunction "IO_3_15") (pintype "bidirectional"))
    )
    (net (code "28") (name "Net-(U1-IO_4)") (class "Default")
      (node (ref "JP1") (pin "1") (pinfunction "1_1") (pintype "passive"))
      (node (ref "U1") (pin "2") (pinfunction "IO_4_2") (pintype "bidirectional"))
    )
    (net (code "29") (name "Net-(U1-IO_5)") (class "Default")
      (node (ref "JP1") (pin "9") (pinfunction "9_9") (pintype "passive"))
      (node (ref "U1") (pin "16") (pinfunction "IO_5_16") (pintype "bidirectional"))
    )
    (net (code "30") (name "Net-(U1-IO_6)") (class "Default")
      (node (ref "JP1") (pin "2") (pinfunction "2_2") (pintype "passive"))
      (node (ref "U1") (pin "3") (pinfunction "IO_6_3") (pintype "bidirectional"))
    )
    (net (code "31") (name "Net-(U1-IO_7)") (class "Default")
      (node (ref "JP1") (pin "10") (pinfunction "10_10") (pintype "passive"))
      (node (ref "U1") (pin "17") (pinfunction "IO_7_17") (pintype "bidirectional"))
    )
    (net (code "32") (name "Net-(U1-IO_8)") (class "Default")
      (node (ref "JP1") (pin "3") (pinfunction "3_3") (pintype "passive"))
      (node (ref "U1") (pin "4") (pinfunction "IO_8_4") (pintype "bidirectional"))
    )
    (net (code "33") (name "Net-(U1-IO_9)") (class "Default")
      (node (ref "JP1") (pin "11") (pinfunction "11_11") (pintype "passive"))
      (node (ref "U1") (pin "18") (pinfunction "IO_9_18") (pintype "bidirectional"))
    )
    (net (code "34") (name "Net-(U1-IO_10)") (class "Default")
      (node (ref "JP1") (pin "4") (pinfunction "4_4") (pintype "passive"))
      (node (ref "U1") (pin "5") (pinfunction "IO_10_5") (pintype "bidirectional"))
    )
    (net (code "35") (name "Net-(U1-IO_11)") (class "Default")
      (node (ref "JP1") (pin "12") (pinfunction "12_12") (pintype "passive"))
      (node (ref "U1") (pin "19") (pinfunction "IO_11_19") (pintype "bidirectional"))
    )
    (net (code "36") (name "Net-(U1-IO_12)") (class "Default")
      (node (ref "JP1") (pin "5") (pinfunction "5_5") (pintype "passive"))
      (node (ref "U1") (pin "6") (pinfunction "IO_12_6") (pintype "bidirectional"))
    )
    (net (code "37") (name "Net-(U1-IO_13)") (class "Default")
      (node (ref "JP1") (pin "13") (pinfunction "13_13") (pintype "passive"))
      (node (ref "U1") (pin "20") (pinfunction "IO_13_20") (pintype "bidirectional"))
    )
    (net (code "38") (name "Net-(U1-IO_14)") (class "Default")
      (node (ref "JP2") (pin "3") (pinfunction "3_3") (pintype "passive"))
      (node (ref "U1") (pin "40") (pinfunction "IO_14_40") (pintype "bidirectional"))
    )
    (net (code "39") (name "Net-(U1-IO_15)") (class "Default")
      (node (ref "JP1") (pin "6") (pinfunction "6_6") (pintype "passive"))
      (node (ref "U1") (pin "7") (pinfunction "IO_15_7") (pintype "bidirectional"))
    )
    (net (code "40") (name "Net-(U1-IO_16)") (class "Default")
      (node (ref "JP2") (pin "4") (pinfunction "4_4") (pintype "passive"))
      (node (ref "U1") (pin "41") (pinfunction "IO_16_41") (pintype "bidirectional"))
    )
    (net (code "41") (name "Net-(U1-IO_17)") (class "Default")
      (node (ref "JP1") (pin "14") (pinfunction "14_14") (pintype "passive"))
      (node (ref "U1") (pin "21") (pinfunction "IO_17_21") (pintype "bidirectional"))
    )
    (net (code "42") (name "Net-(U1-IO_18)") (class "Default")
      (node (ref "JP2") (pin "1") (pinfunction "1_1") (pintype "passive"))
      (node (ref "U1") (pin "42") (pinfunction "IO_18_42") (pintype "bidirectional"))
    )
    (net (code "43") (name "Net-(U1-IO_19)") (class "Default")
      (node (ref "JP1") (pin "7") (pinfunction "7_7") (pintype "passive"))
      (node (ref "U1") (pin "8") (pinfunction "IO_19_8") (pintype "bidirectional"))
    )
    (net (code "44") (name "Net-(U1-IO_20)") (class "Default")
      (node (ref "JP2") (pin "10") (pinfunction "10_10") (pintype "passive"))
      (node (ref "U1") (pin "33") (pinfunction "IO_20_33") (pintype "bidirectional"))
    )
    (net (code "45") (name "Net-(U1-IO_21)") (class "Default")
      (node (ref "JP2") (pin "7") (pinfunction "7_7") (pintype "passive"))
      (node (ref "U1") (pin "34") (pinfunction "IO_21_34") (pintype "bidirectional"))
    )
    (net (code "46") (name "Net-(U1-IO_22)") (class "Default")
      (node (ref "JP2") (pin "8") (pinfunction "8_8") (pintype "passive"))
      (node (ref "U1") (pin "35") (pinfunction "IO_22_35") (pintype "bidirectional"))
    )
    (net (code "47") (name "Net-(U1-IO_23)") (class "Default")
      (node (ref "JP2") (pin "5") (pinfunction "5_5") (pintype "passive"))
      (node (ref "U1") (pin "36") (pinfunction "IO_23_36") (pintype "bidirectional"))
    )
    (net (code "48") (name "Net-(U1-IO_24)") (class "Default")
      (node (ref "LED5") (pin "C") (pinfunction "C_C") (pintype "passive"))
      (node (ref "U1") (pin "47") (pinfunction "IO_24_47") (pintype "bidirectional"))
    )
    (net (code "49") (name "Net-(U1-IO_25)") (class "Default")
      (node (ref "JP2") (pin "13") (pinfunction "13_13") (pintype "passive"))
      (node (ref "U1") (pin "26") (pinfunction "IO_25_26") (pintype "bidirectional"))
    )
    (net (code "50") (name "Net-(U1-IO_26)") (class "Default")
      (node (ref "LED4") (pin "C") (pinfunction "C_C") (pintype "passive"))
      (node (ref "U1") (pin "48") (pinfunction "IO_26_48") (pintype "bidirectional"))
    )
    (net (code "51") (name "Net-(U1-IO_27)") (class "Default")
      (node (ref "JP2") (pin "14") (pinfunction "14_14") (pintype "passive"))
      (node (ref "U1") (pin "27") (pinfunction "IO_27_27") (pintype "bidirectional"))
    )
    (net (code "52") (name "Net-(U1-IO_28)") (class "Default")
      (node (ref "LED3") (pin "C") (pinfunction "C_C") (pintype "passive"))
      (node (ref "U1") (pin "49") (pinfunction "IO_28_49") (pintype "bidirectional"))
    )
    (net (code "53") (name "Net-(U1-IO_29)") (class "Default")
      (node (ref "JP2") (pin "6") (pinfunction "6_6") (pintype "passive"))
      (node (ref "U1") (pin "38") (pinfunction "IO_29_38") (pintype "bidirectional"))
    )
    (net (code "54") (name "Net-(U1-IO_30)") (class "Default")
      (node (ref "LED2") (pin "C") (pinfunction "C_C") (pintype "passive"))
      (node (ref "U1") (pin "50") (pinfunction "IO_30_50") (pintype "bidirectional"))
    )
    (net (code "55") (name "Net-(U1-IO_31)") (class "Default")
      (node (ref "JP2") (pin "11") (pinfunction "11_11") (pintype "passive"))
      (node (ref "U1") (pin "28") (pinfunction "IO_31_28") (pintype "bidirectional"))
    )
    (net (code "56") (name "Net-(U1-IO_32)") (class "Default")
      (node (ref "JP2") (pin "12") (pinfunction "12_12") (pintype "passive"))
      (node (ref "U1") (pin "29") (pinfunction "IO_32_29") (pintype "bidirectional"))
    )
    (net (code "57") (name "Net-(U1-IO_33)") (class "Default")
      (node (ref "JP2") (pin "9") (pinfunction "9_9") (pintype "passive"))
      (node (ref "U1") (pin "30") (pinfunction "IO_33_30") (pintype "bidirectional"))
    )
    (net (code "58") (name "Net-(U1-IO_34)") (class "Default")
      (node (ref "LED1") (pin "C") (pinfunction "C_C") (pintype "passive"))
      (node (ref "U1") (pin "51") (pinfunction "IO_34_51") (pintype "bidirectional"))
    )
    (net (code "59") (name "Net-(U1-IO_35)") (class "Default")
      (node (ref "U1") (pin "52") (pinfunction "IO_35_52") (pintype "bidirectional"))
      (node (ref "U6") (pin "9") (pinfunction "2Y1_9") (pintype "output"))
    )
    (net (code "60") (name "Net-(U1-IO_36)") (class "Default")
      (node (ref "U1") (pin "53") (pinfunction "IO_36_53") (pintype "bidirectional"))
      (node (ref "U6") (pin "8") (pinfunction "1A4_8") (pintype "input"))
    )
    (net (code "61") (name "Net-(U1-IO_37)") (class "Default")
      (node (ref "U1") (pin "54") (pinfunction "IO_37_54") (pintype "bidirectional"))
      (node (ref "U6") (pin "7") (pinfunction "2Y2_7") (pintype "output"))
    )
    (net (code "62") (name "Net-(U1-IO_38)") (class "Default")
      (node (ref "U1") (pin "55") (pinfunction "IO_38_55") (pintype "bidirectional"))
      (node (ref "U6") (pin "6") (pinfunction "1A3_6") (pintype "input"))
    )
    (net (code "63") (name "Net-(U1-IO_39)") (class "Default")
      (node (ref "U1") (pin "56") (pinfunction "IO_39_56") (pintype "bidirectional"))
      (node (ref "U6") (pin "5") (pinfunction "2Y3_5") (pintype "output"))
    )
    (net (code "64") (name "Net-(U1-IO_40)") (class "Default")
      (node (ref "U1") (pin "57") (pinfunction "IO_40_57") (pintype "bidirectional"))
      (node (ref "U6") (pin "4") (pinfunction "1A2_4") (pintype "input"))
    )
    (net (code "65") (name "Net-(U1-IO_41)") (class "Default")
      (node (ref "U1") (pin "58") (pinfunction "IO_41_58") (pintype "bidirectional"))
      (node (ref "U6") (pin "3") (pinfunction "2Y4_3") (pintype "output"))
    )
    (net (code "66") (name "Net-(U1-IO_42)") (class "Default")
      (node (ref "U1") (pin "61") (pinfunction "IO_42_61") (pintype "bidirectional"))
      (node (ref "U6") (pin "2") (pinfunction "1A1_2") (pintype "input"))
    )
    (net (code "67") (name "Net-(U1-IO_43)") (class "Default")
      (node (ref "R33") (pin "2") (pinfunction "2_2") (pintype "passive"))
      (node (ref "U1") (pin "66") (pinfunction "IO_43_66") (pintype "bidirectional"))
      (node (ref "U6") (pin "1") (pinfunction "~{1OE}_1") (pintype "input"))
    )
    (net (code "68") (name "Net-(U1-IO_44)") (class "Default")
      (node (ref "R34") (pin "2") (pinfunction "2_2") (pintype "passive"))
      (node (ref "U1") (pin "67") (pinfunction "IO_44_67") (pintype "bidirectional"))
      (node (ref "U6") (pin "19") (pinfunction "~{2OE}_19") (pintype "input"))
    )
    (net (code "69") (name "Net-(U1-IO_45)") (class "Default")
      (node (ref "U1") (pin "68") (pinfunction "IO_45_68") (pintype "bidirectional"))
      (node (ref "U5") (pin "9") (pinfunction "2Y1_9") (pintype "output"))
    )
    (net (code "70") (name "Net-(U1-IO_46)") (class "Default")
      (node (ref "U1") (pin "69") (pinfunction "IO_46_69") (pintype "bidirectional"))
      (node (ref "U5") (pin "8") (pinfunction "1A4_8") (pintype "input"))
    )
    (net (code "71") (name "Net-(U1-IO_47)") (class "Default")
      (node (ref "U1") (pin "70") (pinfunction "IO_47_70") (pintype "bidirectional"))
      (node (ref "U5") (pin "7") (pinfunction "2Y2_7") (pintype "output"))
    )
    (net (code "72") (name "Net-(U1-IO_48)") (class "Default")
      (node (ref "U1") (pin "71") (pinfunction "IO_48_71") (pintype "bidirectional"))
      (node (ref "U5") (pin "6") (pinfunction "1A3_6") (pintype "input"))
    )
    (net (code "73") (name "Net-(U1-IO_49)") (class "Default")
      (node (ref "U1") (pin "72") (pinfunction "IO_49_72") (pintype "bidirectional"))
      (node (ref "U5") (pin "5") (pinfunction "2Y3_5") (pintype "output"))
    )
    (net (code "74") (name "Net-(U1-IO_50)") (class "Default")
      (node (ref "U1") (pin "73") (pinfunction "IO_50_73") (pintype "bidirectional"))
      (node (ref "U5") (pin "4") (pinfunction "1A2_4") (pintype "input"))
    )
    (net (code "75") (name "Net-(U1-IO_51)") (class "Default")
      (node (ref "U1") (pin "74") (pinfunction "IO_51_74") (pintype "bidirectional"))
      (node (ref "U5") (pin "3") (pinfunction "2Y4_3") (pintype "output"))
    )
    (net (code "76") (name "Net-(U1-IO_52)") (class "Default")
      (node (ref "U1") (pin "75") (pinfunction "IO_52_75") (pintype "bidirectional"))
      (node (ref "U5") (pin "2") (pinfunction "1A1_2") (pintype "input"))
    )
    (net (code "77") (name "Net-(U1-IO_53)") (class "Default")
      (node (ref "R31") (pin "2") (pinfunction "2_2") (pintype "passive"))
      (node (ref "U1") (pin "76") (pinfunction "IO_53_76") (pintype "bidirectional"))
      (node (ref "U5") (pin "1") (pinfunction "~{1OE}_1") (pintype "input"))
    )
    (net (code "78") (name "Net-(U1-IO_54)") (class "Default")
      (node (ref "R32") (pin "2") (pinfunction "2_2") (pintype "passive"))
      (node (ref "U1") (pin "77") (pinfunction "IO_54_77") (pintype "bidirectional"))
      (node (ref "U5") (pin "19") (pinfunction "~{2OE}_19") (pintype "input"))
    )
    (net (code "79") (name "Net-(U1-IO_57)") (class "Default")
      (node (ref "U1") (pin "82") (pinfunction "IO_57_82") (pintype "bidirectional"))
      (node (ref "U2") (pin "34") (pinfunction "ACBUS7_34") (pintype "bidirectional"))
    )
    (net (code "80") (name "Net-(U1-IO_58)") (class "Default")
      (node (ref "U1") (pin "83") (pinfunction "IO_58_83") (pintype "bidirectional"))
      (node (ref "U2") (pin "33") (pinfunction "ACBUS6_33") (pintype "bidirectional"))
    )
    (net (code "81") (name "Net-(U1-IO_59)") (class "Default")
      (node (ref "U1") (pin "84") (pinfunction "IO_59_84") (pintype "bidirectional"))
      (node (ref "U2") (pin "32") (pinfunction "ACBUS5_32") (pintype "bidirectional"))
    )
    (net (code "82") (name "Net-(U1-IO_60)") (class "Default")
      (node (ref "U1") (pin "85") (pinfunction "IO_60_85") (pintype "bidirectional"))
      (node (ref "U2") (pin "30") (pinfunction "ACBUS4_30") (pintype "bidirectional"))
    )
    (net (code "83") (name "Net-(U1-IO_61)") (class "Default")
      (node (ref "U1") (pin "86") (pinfunction "IO_61_86") (pintype "bidirectional"))
      (node (ref "U2") (pin "29") (pinfunction "ACBUS3_29") (pintype "bidirectional"))
    )
    (net (code "84") (name "Net-(U1-IO_62)") (class "Default")
      (node (ref "U1") (pin "87") (pinfunction "IO_62_87") (pintype "bidirectional"))
      (node (ref "U2") (pin "28") (pinfunction "ACBUS2_28") (pintype "bidirectional"))
    )
    (net (code "85") (name "Net-(U1-IO_63)") (class "Default")
      (node (ref "U1") (pin "89") (pinfunction "IO_63_89") (pintype "bidirectional"))
      (node (ref "U2") (pin "27") (pinfunction "ACBUS1_27") (pintype "bidirectional"))
    )
    (net (code "86") (name "Net-(U1-IO_64)") (class "Default")
      (node (ref "U1") (pin "91") (pinfunction "IO_64_91") (pintype "bidirectional"))
      (node (ref "U2") (pin "26") (pinfunction "ACBUS0_26") (pintype "bidirectional"))
    )
    (net (code "87") (name "Net-(U1-IO_65)") (class "Default")
      (node (ref "U1") (pin "92") (pinfunction "IO_65_92") (pintype "bidirectional"))
      (node (ref "U2") (pin "24") (pinfunction "ADBUS7_24") (pintype "bidirectional"))
    )
    (net (code "88") (name "Net-(U1-IO_66)") (class "Default")
      (node (ref "U1") (pin "95") (pinfunction "IO_66_95") (pintype "bidirectional"))
      (node (ref "U2") (pin "23") (pinfunction "ADBUS6_23") (pintype "bidirectional"))
    )
    (net (code "89") (name "Net-(U1-IO_67)") (class "Default")
      (node (ref "U1") (pin "96") (pinfunction "IO_67_96") (pintype "bidirectional"))
      (node (ref "U2") (pin "22") (pinfunction "ADBUS5_22") (pintype "bidirectional"))
    )
    (net (code "90") (name "Net-(U1-IO_68)") (class "Default")
      (node (ref "U1") (pin "97") (pinfunction "IO_68_97") (pintype "bidirectional"))
      (node (ref "U2") (pin "21") (pinfunction "ADBUS4_21") (pintype "bidirectional"))
    )
    (net (code "91") (name "Net-(U1-IO_69)") (class "Default")
      (node (ref "U1") (pin "98") (pinfunction "IO_69_98") (pintype "bidirectional"))
      (node (ref "U2") (pin "19") (pinfunction "ADBUS3_19") (pintype "bidirectional"))
    )
    (net (code "92") (name "Net-(U1-IO_70)") (class "Default")
      (node (ref "U1") (pin "99") (pinfunction "IO_70_99") (pintype "bidirectional"))
      (node (ref "U2") (pin "18") (pinfunction "ADBUS2_18") (pintype "bidirectional"))
    )
    (net (code "93") (name "Net-(U1-IO{slash}DEV_CLRN)") (class "Default")
      (node (ref "R18") (pin "2") (pinfunction "2_2") (pintype "passive"))
      (node (ref "U1") (pin "44") (pinfunction "IO/DEV_CLRN_44") (pintype "bidirectional"))
    )
    (net (code "94") (name "Net-(U1-IO{slash}DEV_OE)") (class "Default")
      (node (ref "R19") (pin "2") (pinfunction "2_2") (pintype "passive"))
      (node (ref "U1") (pin "43") (pinfunction "IO/DEV_OE_43") (pintype "bidirectional"))
    )
    (net (code "95") (name "Net-(U2--RESET)") (class "Default")
      (node (ref "R6") (pin "2") (pinfunction "2_2") (pintype "passive"))
      (node (ref "U2") (pin "14") (pinfunction "-RESET_14") (pintype "input"))
    )
    (net (code "96") (name "Net-(U2-BDBUS0)") (class "Default")
      (node (ref "U2") (pin "38") (pinfunction "BDBUS0_38") (pintype "bidirectional"))
      (node (ref "U9") (pin "2") (pinfunction "A_2") (pintype "input"))
    )
    (net (code "97") (name "Net-(U2-BDBUS5)") (class "Default")
      (node (ref "R7") (pin "1") (pinfunction "1_1") (pintype "passive"))
      (node (ref "U2") (pin "44") (pinfunction "BDBUS5_44") (pintype "bidirectional"))
    )
    (net (code "98") (name "Net-(U2-D+)") (class "Default")
      (node (ref "U2") (pin "8") (pinfunction "D+_8") (pintype "bidirectional"))
      (node (ref "U3") (pin "1") (pinfunction "IO1_1") (pintype "bidirectional"))
      (node (ref "X1") (pin "3") (pinfunction "3_3") (pintype "passive"))
    )
    (net (code "99") (name "Net-(U2-D-)") (class "Default")
      (node (ref "U2") (pin "7") (pinfunction "D-_7") (pintype "bidirectional"))
      (node (ref "U3") (pin "6") (pinfunction "IO2_6") (pintype "bidirectional"))
      (node (ref "X1") (pin "2") (pinfunction "2_2") (pintype "passive"))
    )
    (net (code "100") (name "Net-(U2-REF)") (class "Default")
      (node (ref "R5") (pin "2") (pinfunction "2_2") (pintype "passive"))
      (node (ref "U2") (pin "6") (pinfunction "REF_6") (pintype "input"))
    )
    (net (code "101") (name "Net-(U2-XTIN)") (class "Default")
      (node (ref "C46") (pin "2") (pinfunction "2_2") (pintype "passive"))
      (node (ref "Q1") (pin "2") (pinfunction "2_2") (pintype "passive"))
      (node (ref "U2") (pin "2") (pinfunction "XTIN_2") (pintype "input"))
    )
    (net (code "102") (name "Net-(U2-XTOUT)") (class "Default")
      (node (ref "C45") (pin "2") (pinfunction "2_2") (pintype "passive"))
      (node (ref "Q1") (pin "1") (pinfunction "1_1") (pintype "passive"))
      (node (ref "U2") (pin "3") (pinfunction "XTOUT_3") (pintype "output"))
    )
    (net (code "103") (name "Net-(U3-VP)") (class "Default")
      (node (ref "C1") (pin "2") (pinfunction "2_2") (pintype "passive"))
      (node (ref "F1") (pin "1") (pinfunction "1_1") (pintype "passive"))
      (node (ref "U3") (pin "5") (pinfunction "VP_5") (pintype "bidirectional"))
      (node (ref "X1") (pin "1") (pinfunction "1_1") (pintype "passive"))
    )
    (net (code "104") (name "Net-(U4-DO)") (class "Default")
      (node (ref "R1") (pin "2") (pinfunction "2_2") (pintype "passive"))
      (node (ref "R2") (pin "2") (pinfunction "2_2") (pintype "passive"))
      (node (ref "U4") (pin "4") (pinfunction "DO_4") (pintype "tri_state"))
    )
    (net (code "105") (name "Net-(U5-1Y1)") (class "Default")
      (node (ref "JP3") (pin "4") (pinfunction "4_4") (pintype "passive"))
      (node (ref "U5") (pin "18") (pinfunction "1Y1_18") (pintype "output"))
    )
    (net (code "106") (name "Net-(U5-1Y2)") (class "Default")
      (node (ref "JP3") (pin "6") (pinfunction "6_6") (pintype "passive"))
      (node (ref "U5") (pin "16") (pinfunction "1Y2_16") (pintype "output"))
    )
    (net (code "107") (name "Net-(U5-1Y3)") (class "Default")
      (node (ref "JP3") (pin "8") (pinfunction "8_8") (pintype "passive"))
      (node (ref "U5") (pin "14") (pinfunction "1Y3_14") (pintype "output"))
    )
    (net (code "108") (name "Net-(U5-1Y4)") (class "Default")
      (node (ref "JP3") (pin "10") (pinfunction "10_10") (pintype "passive"))
      (node (ref "U5") (pin "12") (pinfunction "1Y4_12") (pintype "output"))
    )
    (net (code "109") (name "Net-(U5-2A1)") (class "Default")
      (node (ref "JP3") (pin "9") (pinfunction "9_9") (pintype "passive"))
      (node (ref "U5") (pin "11") (pinfunction "2A1_11") (pintype "input"))
    )
    (net (code "110") (name "Net-(U5-2A2)") (class "Default")
      (node (ref "JP3") (pin "7") (pinfunction "7_7") (pintype "passive"))
      (node (ref "U5") (pin "13") (pinfunction "2A2_13") (pintype "input"))
    )
    (net (code "111") (name "Net-(U5-2A3)") (class "Default")
      (node (ref "JP3") (pin "5") (pinfunction "5_5") (pintype "passive"))
      (node (ref "U5") (pin "15") (pinfunction "2A3_15") (pintype "input"))
    )
    (net (code "112") (name "Net-(U5-2A4)") (class "Default")
      (node (ref "JP3") (pin "3") (pinfunction "3_3") (pintype "passive"))
      (node (ref "U5") (pin "17") (pinfunction "2A4_17") (pintype "input"))
    )
    (net (code "113") (name "Net-(U6-1Y1)") (class "Default")
      (node (ref "JP3") (pin "11") (pinfunction "11_11") (pintype "passive"))
      (node (ref "U6") (pin "18") (pinfunction "1Y1_18") (pintype "output"))
    )
    (net (code "114") (name "Net-(U6-1Y2)") (class "Default")
      (node (ref "JP3") (pin "13") (pinfunction "13_13") (pintype "passive"))
      (node (ref "U6") (pin "16") (pinfunction "1Y2_16") (pintype "output"))
    )
    (net (code "115") (name "Net-(U6-1Y3)") (class "Default")
      (node (ref "JP3") (pin "15") (pinfunction "15_15") (pintype "passive"))
      (node (ref "U6") (pin "14") (pinfunction "1Y3_14") (pintype "output"))
    )
    (net (code "116") (name "Net-(U6-1Y4)") (class "Default")
      (node (ref "JP3") (pin "17") (pinfunction "17_17") (pintype "passive"))
      (node (ref "U6") (pin "12") (pinfunction "1Y4_12") (pintype "output"))
    )
    (net (code "117") (name "Net-(U6-2A1)") (class "Default")
      (node (ref "JP3") (pin "18") (pinfunction "18_18") (pintype "passive"))
      (node (ref "U6") (pin "11") (pinfunction "2A1_11") (pintype "input"))
    )
    (net (code "118") (name "Net-(U6-2A2)") (class "Default")
      (node (ref "JP3") (pin "16") (pinfunction "16_16") (pintype "passive"))
      (node (ref "U6") (pin "13") (pinfunction "2A2_13") (pintype "input"))
    )
    (net (code "119") (name "Net-(U6-2A3)") (class "Default")
      (node (ref "JP3") (pin "14") (pinfunction "14_14") (pintype "passive"))
      (node (ref "U6") (pin "15") (pinfunction "2A3_15") (pintype "input"))
    )
    (net (code "120") (name "Net-(U6-2A4)") (class "Default")
      (node (ref "JP3") (pin "12") (pinfunction "12_12") (pintype "passive"))
      (node (ref "U6") (pin "17") (pinfunction "2A4_17") (pintype "input"))
    )
    (net (code "121") (name "Net-(U9-Y)") (class "Default")
      (node (ref "JP4") (pin "9") (pinfunction "9_9") (pintype "passive"))
      (node (ref "U9") (pin "4") (pinfunction "Y_4") (pintype "output"))
    )
    (net (code "122") (name "Net-(U10-A)") (class "Default")
      (node (ref "U10") (pin "2") (pinfunction "A_2") (pintype "input"))
      (node (ref "U2") (pin "39") (pinfunction "BDBUS1_39") (pintype "bidirectional"))
    )
    (net (code "123") (name "Net-(U10-Y)") (class "Default")
      (node (ref "JP4") (pin "5") (pinfunction "5_5") (pintype "passive"))
      (node (ref "U10") (pin "4") (pinfunction "Y_4") (pintype "output"))
    )
    (net (code "124") (name "Net-(U10-~{OE})") (class "Default")
      (node (ref "R17") (pin "1") (pinfunction "1_1") (pintype "passive"))
      (node (ref "U10") (pin "1") (pinfunction "~{OE}_1") (pintype "input"))
      (node (ref "U11") (pin "1") (pinfunction "~{OE}_1") (pintype "input"))
      (node (ref "U12") (pin "1") (pinfunction "~{OE}_1") (pintype "input"))
      (node (ref "U13") (pin "1") (pinfunction "~{OE}_1") (pintype "input"))
      (node (ref "U2") (pin "43") (pinfunction "BDBUS4_43") (pintype "bidirectional"))
      (node (ref "U9") (pin "1") (pinfunction "~{OE}_1") (pintype "input"))
    )
    (net (code "125") (name "Net-(U11-A)") (class "Default")
      (node (ref "JP4") (pin "13") (pinfunction "13_13") (pintype "passive"))
      (node (ref "U11") (pin "2") (pinfunction "A_2") (pintype "input"))
    )
    (net (code "126") (name "Net-(U11-Y)") (class "Default")
      (node (ref "U11") (pin "4") (pinfunction "Y_4") (pintype "output"))
      (node (ref "U2") (pin "40") (pinfunction "BDBUS2_40") (pintype "bidirectional"))
    )
    (net (code "127") (name "Net-(U12-A)") (class "Default")
      (node (ref "U12") (pin "2") (pinfunction "A_2") (pintype "input"))
      (node (ref "U2") (pin "41") (pinfunction "BDBUS3_41") (pintype "bidirectional"))
    )
    (net (code "128") (name "Net-(U12-Y)") (class "Default")
      (node (ref "JP4") (pin "7") (pinfunction "7_7") (pintype "passive"))
      (node (ref "U12") (pin "4") (pinfunction "Y_4") (pintype "output"))
    )
    (net (code "129") (name "Net-(U13-A)") (class "Default")
      (node (ref "JP4") (pin "11") (pinfunction "11_11") (pintype "passive"))
      (node (ref "U13") (pin "2") (pinfunction "A_2") (pintype "input"))
    )
    (net (code "130") (name "Net-(U13-Y)") (class "Default")
      (node (ref "U13") (pin "4") (pinfunction "Y_4") (pintype "output"))
      (node (ref "U2") (pin "46") (pinfunction "BDBUS7_46") (pintype "bidirectional"))
    )
    (net (code "131") (name "Net-(U14-A)") (class "Default")
      (node (ref "U14") (pin "2") (pinfunction "A_2") (pintype "input"))
      (node (ref "U2") (pin "48") (pinfunction "BCBUS0_48") (pintype "bidirectional"))
    )
    (net (code "132") (name "Net-(U14-Y)") (class "Default")
      (node (ref "JP4") (pin "3") (pinfunction "3_3") (pintype "passive"))
      (node (ref "U14") (pin "4") (pinfunction "Y_4") (pintype "output"))
    )
    (net (code "133") (name "Net-(U14-~{OE})") (class "Default")
      (node (ref "U14") (pin "1") (pinfunction "~{OE}_1") (pintype "input"))
      (node (ref "U2") (pin "53") (pinfunction "BCBUS2_53") (pintype "bidirectional"))
    )
    (net (code "134") (name "Net-(U15-A)") (class "Default")
      (node (ref "R15") (pin "2") (pinfunction "2_2") (pintype "passive"))
      (node (ref "U15") (pin "2") (pinfunction "A_2") (pintype "input"))
      (node (ref "U2") (pin "52") (pinfunction "BCBUS1_52") (pintype "bidirectional"))
    )
    (net (code "135") (name "Net-(U15-Y)") (class "Default")
      (node (ref "JP4") (pin "15") (pinfunction "15_15") (pintype "passive"))
      (node (ref "U15") (pin "4") (pinfunction "Y_4") (pintype "output"))
      (node (ref "U16") (pin "2") (pinfunction "A_2") (pintype "input"))
    )
    (net (code "136") (name "Net-(U15-~{OE})") (class "Default")
      (node (ref "R16") (pin "2") (pinfunction "2_2") (pintype "passive"))
      (node (ref "U15") (pin "1") (pinfunction "~{OE}_1") (pintype "input"))
      (node (ref "U2") (pin "54") (pinfunction "BCBUS3_54") (pintype "bidirectional"))
    )
    (net (code "137") (name "Net-(U16-Y)") (class "Default")
      (node (ref "U16") (pin "4") (pinfunction "Y_4") (pintype "output"))
      (node (ref "U2") (pin "45") (pinfunction "BDBUS6_45") (pintype "bidirectional"))
    )
    (net (code "138") (name "VCCINT") (class "Default")
      (node (ref "C51") (pin "1") (pinfunction "1_1") (pintype "passive"))
      (node (ref "C61") (pin "1") (pinfunction "1_1") (pintype "passive"))
      (node (ref "C62") (pin "1") (pinfunction "1_1") (pintype "passive"))
      (node (ref "C63") (pin "1") (pinfunction "1_1") (pintype "passive"))
      (node (ref "C64") (pin "1") (pinfunction "1_1") (pintype "passive"))
      (node (ref "C65") (pin "1") (pinfunction "1_1") (pintype "passive"))
      (node (ref "D1") (pin "1") (pinfunction "A1_1") (pintype "passive"))
      (node (ref "D1") (pin "2") (pinfunction "A2_2") (pintype "passive"))
      (node (ref "IC2") (pin "2") (pinfunction "OUT_2") (pintype "passive"))
      (node (ref "L5") (pin "1") (pinfunction "1_1") (pintype "passive"))
      (node (ref "LED10") (pin "A") (pinfunction "A_A") (pintype "passive"))
      (node (ref "U1") (pin "13") (pinfunction "VCCINT_1_13") (pintype "power_in"))
      (node (ref "U1") (pin "39") (pinfunction "VCCINT_2_39") (pintype "power_in"))
      (node (ref "U1") (pin "63") (pinfunction "VCCINT_3_63") (pintype "power_in"))
      (node (ref "U1") (pin "88") (pinfunction "VCCINT_4_88") (pintype "power_in"))
    )
    (net (code "139") (name "VCCIO") (class "Default")
      (node (ref "C52") (pin "1") (pinfunction "1_1") (pintype "passive"))
      (node (ref "C66") (pin "1") (pinfunction "1_1") (pintype "passive"))
      (node (ref "C67") (pin "1") (pinfunction "1_1") (pintype "passive"))
      (node (ref "C68") (pin "1") (pinfunction "1_1") (pintype "passive"))
      (node (ref "C69") (pin "1") (pinfunction "1_1") (pintype "passive"))
      (node (ref "C70") (pin "1") (pinfunction "1_1") (pintype "passive"))
      (node (ref "C71") (pin "1") (pinfunction "1_1") (pintype "passive"))
      (node (ref "C72") (pin "1") (pinfunction "1_1") (pintype "passive"))
      (node (ref "D1") (pin "3") (pinfunction "C_3") (pintype "passive"))
      (node (ref "JP2") (pin "2") (pinfunction "2_2") (pintype "passive"))
      (node (ref "R18") (pin "1") (pinfunction "1_1") (pintype "passive"))
      (node (ref "R19") (pin "1") (pinfunction "1_1") (pintype "passive"))
      (node (ref "R20") (pin "2") (pinfunction "2_2") (pintype "passive"))
      (node (ref "R21") (pin "2") (pinfunction "2_2") (pintype "passive"))
      (node (ref "R22") (pin "2") (pinfunction "2_2") (pintype "passive"))
      (node (ref "R23") (pin "1") (pinfunction "1_1") (pintype "passive"))
      (node (ref "R24") (pin "1") (pinfunction "1_1") (pintype "passive"))
      (node (ref "R27") (pin "1") (pinfunction "1_1") (pintype "passive"))
      (node (ref "R28") (pin "1") (pinfunction "1_1") (pintype "passive"))
      (node (ref "R29") (pin "1") (pinfunction "1_1") (pintype "passive"))
      (node (ref "U$2") (pin "4") (pinfunction "VCC_4") (pintype "bidirectional"))
      (node (ref "U1") (pin "31") (pinfunction "VCCIO1_2_31") (pintype "power_in"))
      (node (ref "U1") (pin "45") (pinfunction "VCCIO1_3_45") (pintype "power_in"))
      (node (ref "U1") (pin "59") (pinfunction "VCCIO2_1_59") (pintype "power_in"))
      (node (ref "U1") (pin "80") (pinfunction "VCCIO2_2_80") (pintype "power_in"))
      (node (ref "U1") (pin "9") (pinfunction "VCCIO1_1_9") (pintype "power_in"))
      (node (ref "U1") (pin "94") (pinfunction "VCCIO2_3_94") (pintype "power_in"))
    )
    (net (code "140") (name "VCORE") (class "Default")
      (node (ref "C40") (pin "1") (pinfunction "1_1") (pintype "passive"))
      (node (ref "C41") (pin "1") (pinfunction "1_1") (pintype "passive"))
      (node (ref "C42") (pin "1") (pinfunction "1_1") (pintype "passive"))
      (node (ref "C43") (pin "1") (pinfunction "1_1") (pintype "passive"))
      (node (ref "C6") (pin "1") (pinfunction "1_1") (pintype "passive"))
      (node (ref "U2") (pin "12") (pinfunction "VCORE_12") (pintype "power_in"))
      (node (ref "U2") (pin "37") (pinfunction "VCORE_37") (pintype "power_in"))
      (node (ref "U2") (pin "49") (pinfunction "VREGOUT_49") (pintype "passive"))
      (node (ref "U2") (pin "64") (pinfunction "VCORE_64") (pintype "power_in"))
    )
    (net (code "141") (name "VEXT") (class "Default")
      (node (ref "C80") (pin "1") (pinfunction "1_1") (pintype "passive"))
      (node (ref "C81") (pin "1") (pinfunction "1_1") (pintype "passive"))
      (node (ref "JP3") (pin "2") (pinfunction "2_2") (pintype "passive"))
      (node (ref "R31") (pin "1") (pinfunction "1_1") (pintype "passive"))
      (node (ref "R32") (pin "1") (pinfunction "1_1") (pintype "passive"))
      (node (ref "R33") (pin "1") (pinfunction "1_1") (pintype "passive"))
      (node (ref "R34") (pin "1") (pinfunction "1_1") (pintype "passive"))
      (node (ref "U5") (pin "20") (pinfunction "VCC_20") (pintype "power_in"))
      (node (ref "U6") (pin "20") (pinfunction "VCC_20") (pintype "power_in"))
    )
    (net (code "142") (name "VREF") (class "Default")
      (node (ref "C20") (pin "1") (pinfunction "1_1") (pintype "passive"))
      (node (ref "C21") (pin "1") (pinfunction "1_1") (pintype "passive"))
      (node (ref "JP4") (pin "1") (pinfunction "1_1") (pintype "passive"))
      (node (ref "JP4") (pin "2") (pinfunction "2_2") (pintype "passive"))
      (node (ref "R15") (pin "1") (pinfunction "1_1") (pintype "passive"))
      (node (ref "R16") (pin "1") (pinfunction "1_1") (pintype "passive"))
      (node (ref "R17") (pin "2") (pinfunction "2_2") (pintype "passive"))
      (node (ref "R7") (pin "2") (pinfunction "2_2") (pintype "passive"))
      (node (ref "U10") (pin "5") (pinfunction "VCC_5") (pintype "power_in"))
      (node (ref "U11") (pin "5") (pinfunction "VCC_5") (pintype "power_in"))
      (node (ref "U12") (pin "5") (pinfunction "VCC_5") (pintype "power_in"))
      (node (ref "U13") (pin "5") (pinfunction "VCC_5") (pintype "power_in"))
      (node (ref "U14") (pin "5") (pinfunction "VCC_5") (pintype "power_in"))
      (node (ref "U15") (pin "5") (pinfunction "VCC_5") (pintype "power_in"))
      (node (ref "U16") (pin "5") (pinfunction "VCC_5") (pintype "power_in"))
      (node (ref "U9") (pin "5") (pinfunction "VCC_5") (pintype "power_in"))
    )
    (net (code "143") (name "unconnected-(JP4-Pad17)") (class "Default")
      (node (ref "JP4") (pin "17") (pinfunction "17_17") (pintype "passive"))
    )
    (net (code "144") (name "unconnected-(JP4-Pad19)") (class "Default")
      (node (ref "JP4") (pin "19") (pinfunction "19_19") (pintype "passive"))
    )
    (net (code "145") (name "unconnected-(S3A-S-Pad1)") (class "Default")
      (node (ref "S3") (pin "1") (pinfunction "S_1") (pintype "passive"))
    )
    (net (code "146") (name "unconnected-(S3B-S-Pad4)") (class "Default")
      (node (ref "S3") (pin "4") (pinfunction "S_4") (pintype "passive"))
    )
    (net (code "147") (name "unconnected-(U$2-NC1-Pad7)") (class "Default")
      (node (ref "U$2") (pin "7") (pinfunction "NC1_7") (pintype "no_connect"))
    )
    (net (code "148") (name "unconnected-(U$2-NC2-Pad8)") (class "Default")
      (node (ref "U$2") (pin "8") (pinfunction "NC2_8") (pintype "no_connect"))
    )
    (net (code "149") (name "unconnected-(U$2-NC3-Pad6)") (class "Default")
      (node (ref "U$2") (pin "6") (pinfunction "NC3_6") (pintype "no_connect"))
    )
    (net (code "150") (name "unconnected-(U1-IO_55-Pad78)") (class "Default")
      (node (ref "U1") (pin "78") (pinfunction "IO_55_78") (pintype "bidirectional"))
    )
    (net (code "151") (name "unconnected-(U1-IO_56-Pad81)") (class "Default")
      (node (ref "U1") (pin "81") (pinfunction "IO_56_81") (pintype "bidirectional"))
    )
    (net (code "152") (name "unconnected-(U1-IO{slash}GCLK1-Pad14)") (class "Default")
      (node (ref "U1") (pin "14") (pinfunction "IO/GCLK1_14") (pintype "bidirectional"))
    )
    (net (code "153") (name "unconnected-(U1-IO{slash}GCLK2-Pad62)") (class "Default")
      (node (ref "U1") (pin "62") (pinfunction "IO/GCLK2_62") (pintype "bidirectional"))
    )
    (net (code "154") (name "unconnected-(U1-IO{slash}GCLK3-Pad64)") (class "Default")
      (node (ref "U1") (pin "64") (pinfunction "IO/GCLK3_64") (pintype "bidirectional"))
    )
    (net (code "155") (name "unconnected-(U2--PWREN-Pad60)") (class "Default")
      (node (ref "U2") (pin "60") (pinfunction "-PWREN_60") (pintype "output"))
    )
    (net (code "156") (name "unconnected-(U2--SUSPEND-Pad36)") (class "Default")
      (node (ref "U2") (pin "36") (pinfunction "-SUSPEND_36") (pintype "output"))
    )
    (net (code "157") (name "unconnected-(U2-BCBUS4-Pad55)") (class "Default")
      (node (ref "U2") (pin "55") (pinfunction "BCBUS4_55") (pintype "bidirectional"))
    )
    (net (code "158") (name "unconnected-(U2-BCBUS5-Pad57)") (class "Default")
      (node (ref "U2") (pin "57") (pinfunction "BCBUS5_57") (pintype "bidirectional"))
    )
    (net (code "159") (name "unconnected-(U2-BCBUS6-Pad58)") (class "Default")
      (node (ref "U2") (pin "58") (pinfunction "BCBUS6_58") (pintype "bidirectional"))
    )
    (net (code "160") (name "unconnected-(U2-PWRSAVE{slash}BCBUS7-Pad59)") (class "Default")
      (node (ref "U2") (pin "59") (pinfunction "PWRSAVE/BCBUS7_59") (pintype "bidirectional"))
    )
    (net (code "161") (name "unconnected-(U3-NC-Pad3)") (class "Default")
      (node (ref "U3") (pin "3") (pinfunction "NC_3") (pintype "bidirectional"))
    )
    (net (code "162") (name "unconnected-(U3-NC2-Pad4)") (class "Default")
      (node (ref "U3") (pin "4") (pinfunction "NC2_4") (pintype "bidirectional"))
    )
    (net (code "163") (name "unconnected-(U4-NC-Pad7)") (class "Default")
      (node (ref "U4") (pin "7") (pinfunction "NC_7") (pintype "bidirectional"))
    )
    (net (code "164") (name "unconnected-(U4-ORG-Pad6)") (class "Default")
      (node (ref "U4") (pin "6") (pinfunction "ORG_6") (pintype "bidirectional"))
    )
  )
)
